# LORA.net
KiCad netlist of a schematic drawn in Altium Designer
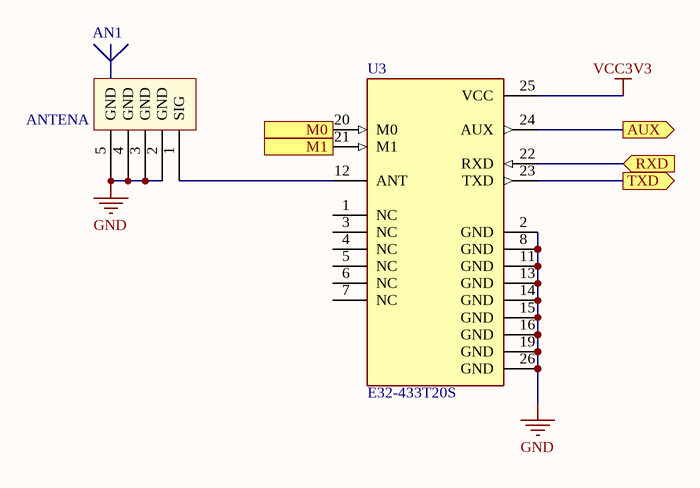
[diagram p0: LORA.SchDoc]

(export (version "E")
  (design (tool "Eeschema 10.0.6"))
  (components
    (comp (ref "AN1")
      (value "ANTENA")
      (footprint "De Anten SMA SMD")
      (description "Generic Antenna")
      (libsource (lib "Altium_Lib_by_KhueNguyenCreator") (part "ANTEN SMA THANG"))
    )
    (comp (ref "U3")
      (value "E32-433T20S")
      (footprint "MODULE_E32-433T20S")
      (description "Wireless serial port module (UART)")
      (fields (field (name "MF") "EBYTE"))
      (libsource (lib "E32-433T20S") (part "E32-433T20S"))
    )
  )
  (nets
    (net (code "1") (name "/AUX") (class "Default")
      (node (ref "U3") (pin "24") (pinfunction "AUX_24") (pintype "output"))
    )
    (net (code "2") (name "/M0") (class "Default")
      (node (ref "U3") (pin "20") (pinfunction "M0_20") (pintype "input"))
    )
    (net (code "3") (name "/M1") (class "Default")
      (node (ref "U3") (pin "21") (pinfunction "M1_21") (pintype "input"))
    )
    (net (code "4") (name "/RXD") (class "Default")
      (node (ref "U3") (pin "22") (pinfunction "RXD_22") (pintype "input"))
    )
    (net (code "5") (name "/TXD") (class "Default")
      (node (ref "U3") (pin "23") (pinfunction "TXD_23") (pintype "output"))
    )
    (net (code "6") (name "GND") (class "Default")
      (node (ref "AN1") (pin "2") (pinfunction "GND_2") (pintype "passive"))
      (node (ref "AN1") (pin "3") (pinfunction "GND_3") (pintype "passive"))
      (node (ref "AN1") (pin "4") (pinfunction "GND_4") (pintype "passive"))
      (node (ref "AN1") (pin "5") (pinfunction "GND_5") (pintype "passive"))
      (node (ref "U3") (pin "11") (pinfunction "GND_11") (pintype "power_in"))
      (node (ref "U3") (pin "13") (pinfunction "GND_13") (pintype "power_in"))
      (node (ref "U3") (pin "14") (pinfunction "GND_14") (pintype "power_in"))
      (node (ref "U3") (pin "15") (pinfunction "GND_15") (pintype "power_in"))
      (node (ref "U3") (pin "16") (pinfunction "GND_16") (pintype "power_in"))
      (node (ref "U3") (pin "19") (pinfunction "GND_19") (pintype "power_in"))
      (node (ref "U3") (pin "2") (pinfunction "GND_2") (pintype "power_in"))
      (node (ref "U3") (pin "26") (pinfunction "GND_26") (pintype "power_in"))
      (node (ref "U3") (pin "8") (pinfunction "GND_8") (pintype "power_in"))
    )
    (net (code "7") (name "Net-(AN1-SIG)") (class "Default")
      (node (ref "AN1") (pin "1") (pinfunction "SIG_1") (pintype "passive"))
      (node (ref "U3") (pin "12") (pinfunction "ANT_12") (pintype "passive"))
    )
    (net (code "8") (name "VCC3V3") (class "Default")
      (node (ref "U3") (pin "25") (pinfunction "VCC_25") (pintype "power_in"))
    )
    (net (code "9") (name "unconnected-(U3-NC-Pad1)") (class "Default")
      (node (ref "U3") (pin "1") (pinfunction "NC_1") (pintype "passive"))
    )
    (net (code "10") (name "unconnected-(U3-NC-Pad3)") (class "Default")
      (node (ref "U3") (pin "3") (pinfunction "NC_3") (pintype "passive"))
    )
    (net (code "11") (name "unconnected-(U3-NC-Pad4)") (class "Default")
      (node (ref "U3") (pin "4") (pinfunction "NC_4") (pintype "passive"))
    )
    (net (code "12") (name "unconnected-(U3-NC-Pad5)") (class "Default")
      (node (ref "U3") (pin "5") (pinfunction "NC_5") (pintype "passive"))
    )
    (net (code "13") (name "unconnected-(U3-NC-Pad6)") (class "Default")
      (node (ref "U3") (pin "6") (pinfunction "NC_6") (pintype "passive"))
    )
    (net (code "14") (name "unconnected-(U3-NC-Pad7)") (class "Default")
      (node (ref "U3") (pin "7") (pinfunction "NC_7") (pintype "passive"))
    )
  )
)
